# SHDN-IMD-S02-V00-IMDConnection.net
KiCad netlist of a schematic drawn in Altium Designer
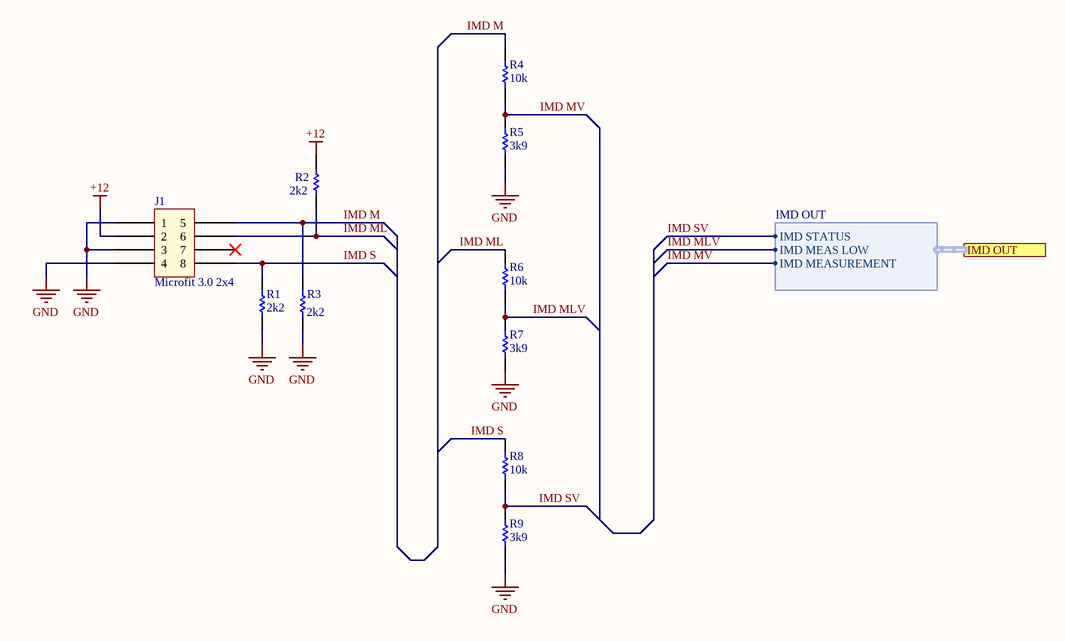
[diagram p0: SHDN-IMD-S02-V00-IMDConnection.SchDoc]

(export (version "E")
  (design (tool "Eeschema 10.0.6"))
  (components
    (comp (ref "J1")
      (value "Microfit 3.0 2x4")
      (footprint "Microfit_2X4_R_TH")
      (libsource (lib "QUTMS_MicrofitLibrary") (part "Microfit_2x4"))
    )
    (comp (ref "R1")
      (value "2k2")
      (footprint "Res_ThinFilm_0603")
      (description "Resistor, SMD, 2k2, 0.1W, 5%, 0603")
      (libsource (lib "StandardResistors") (part "2k2 5% 0603"))
    )
    (comp (ref "R2")
      (value "2k2")
      (footprint "Res_ThinFilm_0603")
      (description "Resistor, SMD, 2k2, 0.1W, 5%, 0603")
      (libsource (lib "StandardResistors") (part "2k2 5% 0603"))
    )
    (comp (ref "R3")
      (value "2k2")
      (footprint "Res_ThinFilm_0603")
      (description "Resistor, SMD, 2k2, 0.1W, 5%, 0603")
      (libsource (lib "StandardResistors") (part "2k2 5% 0603"))
    )
    (comp (ref "R4")
      (value "10k")
      (footprint "Res_ThinFilm_0603")
      (description "Resistor, SMD, 10k, 0.1W, 1%, 0603")
      (libsource (lib "StandardResistors") (part "10k 1% 0603"))
    )
    (comp (ref "R5")
      (value "3k9")
      (footprint "Res_ThinFilm_0603")
      (description "Resistor, SMD, 3k9, 0.1W, 5%, 0603")
      (libsource (lib "StandardResistors") (part "3k9 5% 0603"))
    )
    (comp (ref "R6")
      (value "10k")
      (footprint "Res_ThinFilm_0603")
      (description "Resistor, SMD, 10k, 0.1W, 1%, 0603")
      (libsource (lib "StandardResistors") (part "10k 1% 0603"))
    )
    (comp (ref "R7")
      (value "3k9")
      (footprint "Res_ThinFilm_0603")
      (description "Resistor, SMD, 3k9, 0.1W, 5%, 0603")
      (libsource (lib "StandardResistors") (part "3k9 5% 0603"))
    )
    (comp (ref "R8")
      (value "10k")
      (footprint "Res_ThinFilm_0603")
      (description "Resistor, SMD, 10k, 0.1W, 1%, 0603")
      (libsource (lib "StandardResistors") (part "10k 1% 0603"))
    )
    (comp (ref "R9")
      (value "3k9")
      (footprint "Res_ThinFilm_0603")
      (description "Resistor, SMD, 3k9, 0.1W, 5%, 0603")
      (libsource (lib "StandardResistors") (part "3k9 5% 0603"))
    )
  )
  (nets
    (net (code "3") (name "+12") (class "Default")
      (node (ref "J1") (pin "2") (pinfunction "2_2") (pintype "passive"))
      (node (ref "R2") (pin "2") (pinfunction "2_2") (pintype "passive"))
    )
    (net (code "4") (name "/IMD M") (class "Default")
      (node (ref "J1") (pin "5") (pinfunction "5_5") (pintype "passive"))
      (node (ref "R3") (pin "2") (pinfunction "2_2") (pintype "passive"))
      (node (ref "R4") (pin "2") (pinfunction "2_2") (pintype "passive"))
    )
    (net (code "5") (name "/IMD ML") (class "Default")
      (node (ref "J1") (pin "6") (pinfunction "6_6") (pintype "passive"))
      (node (ref "R2") (pin "1") (pinfunction "1_1") (pintype "passive"))
      (node (ref "R6") (pin "2") (pinfunction "2_2") (pintype "passive"))
    )
    (net (code "6") (name "/IMD MLV") (class "Default")
      (node (ref "R6") (pin "1") (pinfunction "1_1") (pintype "passive"))
      (node (ref "R7") (pin "2") (pinfunction "2_2") (pintype "passive"))
    )
    (net (code "7") (name "/IMD MV") (class "Default")
      (node (ref "R4") (pin "1") (pinfunction "1_1") (pintype "passive"))
      (node (ref "R5") (pin "2") (pinfunction "2_2") (pintype "passive"))
    )
    (net (code "8") (name "/IMD S") (class "Default")
      (node (ref "J1") (pin "8") (pinfunction "8_8") (pintype "passive"))
      (node (ref "R1") (pin "2") (pinfunction "2_2") (pintype "passive"))
      (node (ref "R8") (pin "2") (pinfunction "2_2") (pintype "passive"))
    )
    (net (code "9") (name "/IMD SV") (class "Default")
      (node (ref "R8") (pin "1") (pinfunction "1_1") (pintype "passive"))
      (node (ref "R9") (pin "2") (pinfunction "2_2") (pintype "passive"))
    )
    (net (code "11") (name "GND") (class "Default")
      (node (ref "J1") (pin "1") (pinfunction "1_1") (pintype "passive"))
      (node (ref "J1") (pin "3") (pinfunction "3_3") (pintype "passive"))
      (node (ref "J1") (pin "4") (pinfunction "4_4") (pintype "passive"))
      (node (ref "R1") (pin "1") (pinfunction "1_1") (pintype "passive"))
      (node (ref "R3") (pin "1") (pinfunction "1_1") (pintype "passive"))
      (node (ref "R5") (pin "1") (pinfunction "1_1") (pintype "passive"))
      (node (ref "R7") (pin "1") (pinfunction "1_1") (pintype "passive"))
      (node (ref "R9") (pin "1") (pinfunction "1_1") (pintype "passive"))
    )
    (net (code "12") (name "unconnected-(J1-Pad7)") (class "Default")
      (node (ref "J1") (pin "7") (pinfunction "7_7") (pintype "passive+no_connect"))
    )
  )
)
